# lessbadschematic.net
KiCad netlist of a schematic drawn in Altium Designer
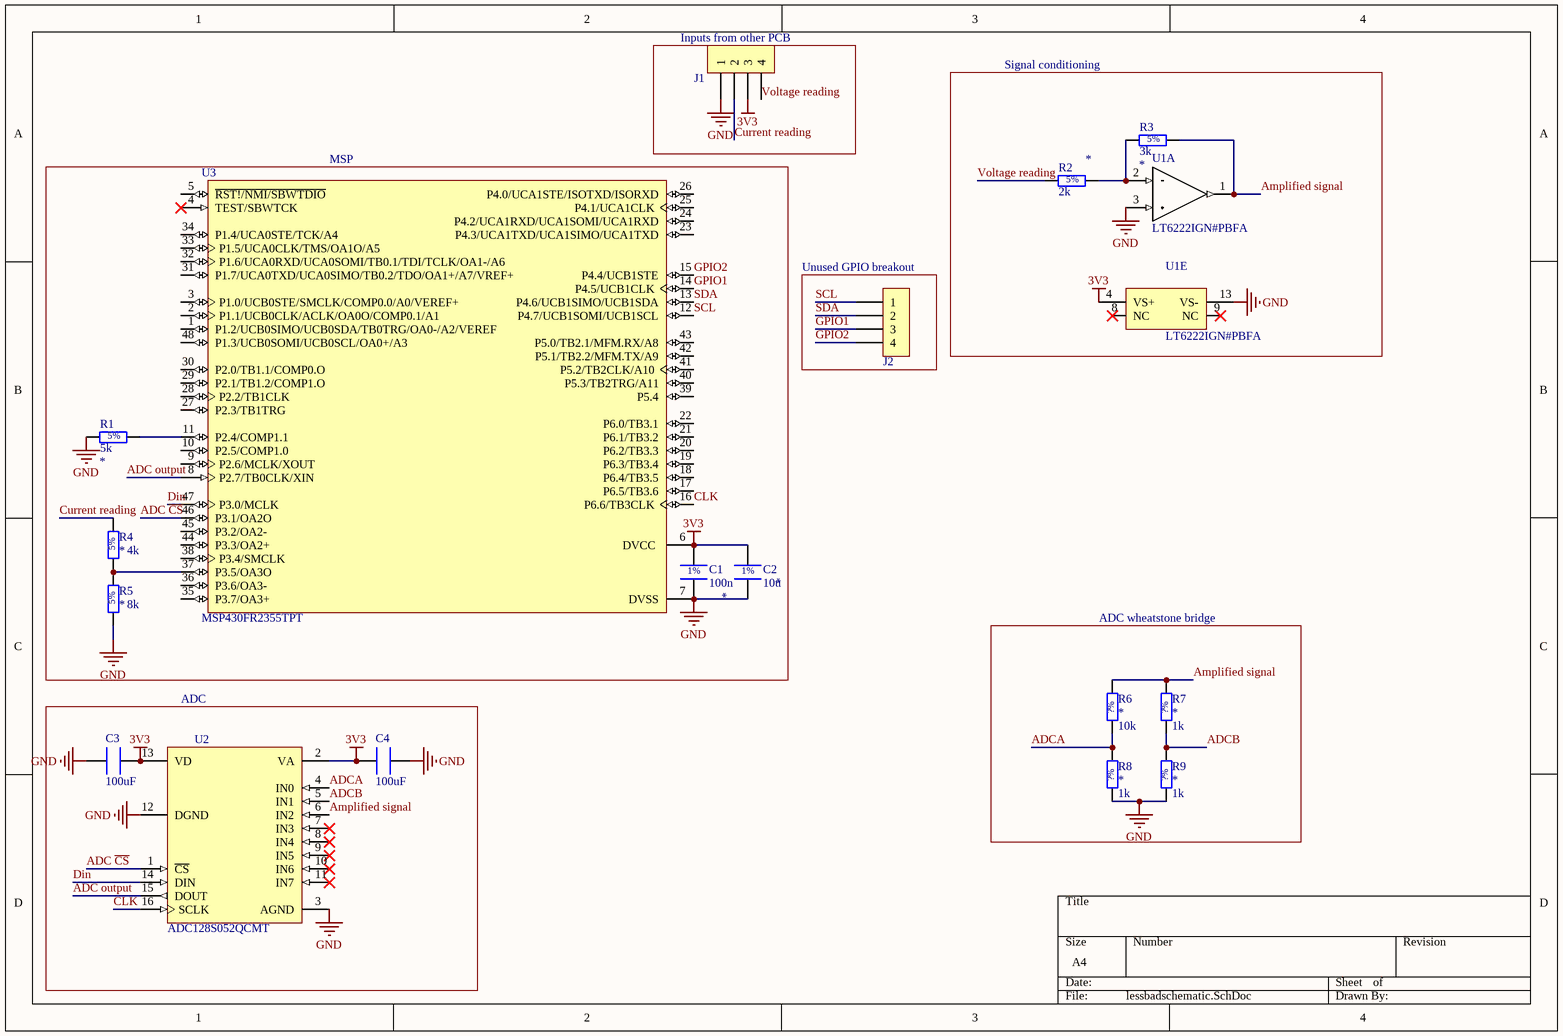
[diagram p0: lessbadschematic.SchDoc]

(export (version "E")
  (design (tool "Eeschema 10.0.6"))
  (components
    (comp (ref "C1")
      (value "100n")
      (footprint "APSS Flight Parts:CAPACITOR_0402_1005M_55N")
      (description "Passive - Capacitor Series, 0402, C0G, 50V, ±1%, -55°C ~ 125°C, 0402 (1005 Metric)")
      (fields (field (name "TOLERANCE") "±1%") (field (name "MF PART NO.") "*"))
      (libsource (lib "APSS Flight Parts") (part "GCM1555CxxxxxF Series"))
    )
    (comp (ref "C2")
      (value "10u")
      (footprint "APSS Flight Parts:CAPACITOR_0402_1005M_55N")
      (description "Passive - Capacitor Series, 0402, C0G, 50V, ±1%, -55°C ~ 125°C, 0402 (1005 Metric)")
      (fields (field (name "TOLERANCE") "±1%") (field (name "MF PART NO.") "*"))
      (libsource (lib "APSS Flight Parts") (part "GCM1555CxxxxxF Series"))
    )
    (comp (ref "C3")
      (value "100uF")
      (footprint "APSS Flight Parts:CAPACITOR_0805_2012M-70N")
      (fields (field (name "TOLERANCE") "±20%") (field (name "MF PART NO.") "GRM21BR60J107ME15L"))
      (libsource (lib "APSS Flight Parts") (part "GRM21BR60J107ME15L"))
    )
    (comp (ref "C4")
      (value "100uF")
      (footprint "APSS Flight Parts:CAPACITOR_0805_2012M-70N")
      (fields (field (name "TOLERANCE") "±20%") (field (name "MF PART NO.") "GRM21BR60J107ME15L"))
      (libsource (lib "APSS Flight Parts") (part "GRM21BR60J107ME15L"))
    )
    (comp (ref "J1")
      (value "0530470410")
      (footprint "APSS Flight Parts:MOLEX_0530470410")
      (description "Header - Picoblade 04-pin, TH, STR")
      (libsource (lib "") (part "0530470410_1"))
    )
    (comp (ref "J2")
      (value "0530470410")
      (footprint "APSS Flight Parts:MOLEX_0530470410")
      (description "Header - Picoblade 04-pin, TH, STR")
      (libsource (lib "APSS Flight Parts") (part "0530470410"))
    )
    (comp (ref "R1")
      (value "5k")
      (footprint "APSS Flight Parts:RESISTOR_0402_1005M_37N")
      (fields (field (name "TOLERANCE") "5%") (field (name "POWER") "1/16W") (field (name "MF PART NO.") "*"))
      (libsource (lib "APSS Flight Parts") (part "RMCF0402JT Series"))
    )
    (comp (ref "R2")
      (value "2k")
      (footprint "APSS Flight Parts:RESISTOR_0402_1005M_37N")
      (fields (field (name "TOLERANCE") "5%") (field (name "POWER") "1/16W") (field (name "MF PART NO.") "*"))
      (libsource (lib "APSS Flight Parts") (part "RMCF0402JT Series"))
    )
    (comp (ref "R3")
      (value "3k")
      (footprint "APSS Flight Parts:RESISTOR_0402_1005M_37N")
      (fields (field (name "TOLERANCE") "5%") (field (name "POWER") "1/16W") (field (name "MF PART NO.") "*"))
      (libsource (lib "APSS Flight Parts") (part "RMCF0402JT Series"))
    )
    (comp (ref "R4")
      (value "*")
      (footprint "APSS Flight Parts:Resistor_0805_2012M-50N")
      (fields
        (field (name "TOLERANCE") "5%")
        (field (name "POWER") "1/8W")
        (field (name "MF PART NO.") "4k")
        (field (name "ALTIUM_VALUE") "*")
      )
      (libsource (lib "APSS Flight Parts") (part "RMCF0805JT Series"))
    )
    (comp (ref "R5")
      (value "*")
      (footprint "APSS Flight Parts:Resistor_0805_2012M-50N")
      (fields
        (field (name "TOLERANCE") "5%")
        (field (name "POWER") "1/8W")
        (field (name "MF PART NO.") "8k")
        (field (name "ALTIUM_VALUE") "*")
      )
      (libsource (lib "APSS Flight Parts") (part "RMCF0805JT Series"))
    )
    (comp (ref "R6")
      (value "*")
      (footprint "RESISTOR_0805_2012M-50N")
      (description "Passive - Resistor, Generic")
      (fields
        (field (name "TOLERANCE") "?%")
        (field (name "MF PART NO.") "10k")
        (field (name "ALTIUM_VALUE") "*")
      )
      (libsource (lib "APSS Generic Components") (part "Generic Resistor"))
    )
    (comp (ref "R7")
      (value "*")
      (footprint "RESISTOR_0805_2012M-50N")
      (description "Passive - Resistor, Generic")
      (fields
        (field (name "TOLERANCE") "?%")
        (field (name "MF PART NO.") "1k")
        (field (name "ALTIUM_VALUE") "*")
      )
      (libsource (lib "APSS Generic Components") (part "Generic Resistor"))
    )
    (comp (ref "R8")
      (value "*")
      (footprint "RESISTOR_0805_2012M-50N")
      (description "Passive - Resistor, Generic")
      (fields
        (field (name "TOLERANCE") "?%")
        (field (name "MF PART NO.") "1k")
        (field (name "ALTIUM_VALUE") "*")
      )
      (libsource (lib "APSS Generic Components") (part "Generic Resistor"))
    )
    (comp (ref "R9")
      (value "*")
      (footprint "RESISTOR_0805_2012M-50N")
      (description "Passive - Resistor, Generic")
      (fields
        (field (name "TOLERANCE") "?%")
        (field (name "MF PART NO.") "1k")
        (field (name "ALTIUM_VALUE") "*")
      )
      (libsource (lib "APSS Generic Components") (part "Generic Resistor"))
    )
    (comp (ref "U1")
      (value "LT6222IGN#PBFA")
      (footprint "APSS Flight Parts:SSOP-16N-3.9mmBody-1.75mm")
      (description "IC - Opamp, High Speed, 4-Channel, 60MHz GBWP, RRIO, 2.2V to 12.6V, -40 to 85, SSOP-16")
      (fields (field (name "MF PART NO.") "LT6222IGN#PBF"))
      (libsource (lib "APSS Flight Parts") (part "LT6222IGN#PBF"))
    )
    (comp (ref "U2")
      (value "ADC128S052QCMT")
      (footprint "APSS Flight Parts:TSSOP-16N_4.4mmBody-1.2mm")
      (description "IC - ADC, 8-Channel, 12-bit, SPI, Split digital/analog Vcc")
      (fields (field (name "MF PART NO.") "ADC128S052QCMT/NOPB-ND"))
      (libsource (lib "APSS Flight Parts") (part "ADC128S052QCMT"))
    )
    (comp (ref "U3")
      (value "MSP430FR2355TPT")
      (footprint "APSS Flight Parts:LQFP_PT_48_N")
      (libsource (lib "APSS Flight Parts") (part "MSP430FR2355TPT"))
    )
  )
  (nets
    (net (code "1") (name "/ADC output") (class "Default")
      (node (ref "U2") (pin "15") (pinfunction "DOUT_15") (pintype "output"))
      (node (ref "U3") (pin "8") (pinfunction "P2.7/TB0CLK/XIN_8") (pintype "input"))
    )
    (net (code "2") (name "/ADC ~{CS}") (class "Default")
      (node (ref "U2") (pin "1") (pinfunction "~{CS}_1") (pintype "input"))
      (node (ref "U3") (pin "46") (pinfunction "P3.1/OA2O_46") (pintype "bidirectional"))
    )
    (net (code "3") (name "/ADCA") (class "Default")
      (node (ref "R6") (pin "1") (pinfunction "1_1") (pintype "passive"))
      (node (ref "R8") (pin "2") (pinfunction "2_2") (pintype "passive"))
      (node (ref "U2") (pin "4") (pinfunction "IN0_4") (pintype "input"))
    )
    (net (code "4") (name "/ADCB") (class "Default")
      (node (ref "R7") (pin "1") (pinfunction "1_1") (pintype "passive"))
      (node (ref "R9") (pin "2") (pinfunction "2_2") (pintype "passive"))
      (node (ref "U2") (pin "5") (pinfunction "IN1_5") (pintype "input"))
    )
    (net (code "5") (name "/Amplified signal") (class "Default")
      (node (ref "R3") (pin "2") (pinfunction "2_2") (pintype "passive"))
      (node (ref "R6") (pin "2") (pinfunction "2_2") (pintype "passive"))
      (node (ref "R7") (pin "2") (pinfunction "2_2") (pintype "passive"))
      (node (ref "U1") (pin "1") (pinfunction "OUT1_1") (pintype "output"))
      (node (ref "U2") (pin "6") (pinfunction "IN2_6") (pintype "input"))
    )
    (net (code "6") (name "/CLK") (class "Default")
      (node (ref "U2") (pin "16") (pinfunction "SCLK_16") (pintype "input"))
      (node (ref "U3") (pin "16") (pinfunction "P6.6/TB3CLK_16") (pintype "bidirectional"))
    )
    (net (code "7") (name "/Current reading") (class "Default")
      (node (ref "J1") (pin "2") (pinfunction "2_2") (pintype "passive"))
      (node (ref "R4") (pin "2") (pinfunction "2_2") (pintype "passive"))
    )
    (net (code "8") (name "/Din") (class "Default")
      (node (ref "U2") (pin "14") (pinfunction "DIN_14") (pintype "input"))
      (node (ref "U3") (pin "47") (pinfunction "P3.0/MCLK_47") (pintype "bidirectional"))
    )
    (net (code "9") (name "/GPIO1") (class "Default")
      (node (ref "J2") (pin "3") (pinfunction "3_3") (pintype "passive"))
      (node (ref "U3") (pin "14") (pinfunction "P4.5/UCB1CLK_14") (pintype "bidirectional"))
    )
    (net (code "10") (name "/GPIO2") (class "Default")
      (node (ref "J2") (pin "4") (pinfunction "4_4") (pintype "passive"))
      (node (ref "U3") (pin "15") (pinfunction "P4.4/UCB1STE_15") (pintype "bidirectional"))
    )
    (net (code "11") (name "/SCL") (class "Default")
      (node (ref "J2") (pin "1") (pinfunction "1_1") (pintype "passive"))
      (node (ref "U3") (pin "12") (pinfunction "P4.7/UCB1SOMI/UCB1SCL_12") (pintype "bidirectional"))
    )
    (net (code "12") (name "/SDA") (class "Default")
      (node (ref "J2") (pin "2") (pinfunction "2_2") (pintype "passive"))
      (node (ref "U3") (pin "13") (pinfunction "P4.6/UCB1SIMO/UCB1SDA_13") (pintype "bidirectional"))
    )
    (net (code "13") (name "/Voltage reading") (class "Default")
      (node (ref "J1") (pin "4") (pinfunction "4_4") (pintype "passive"))
      (node (ref "R2") (pin "1") (pinfunction "1_1") (pintype "passive"))
    )
    (net (code "14") (name "3V3") (class "Default")
      (node (ref "C1") (pin "2") (pinfunction "2_2") (pintype "passive"))
      (node (ref "C2") (pin "2") (pinfunction "2_2") (pintype "passive"))
      (node (ref "C3") (pin "2") (pinfunction "2_2") (pintype "passive"))
      (node (ref "C4") (pin "1") (pinfunction "1_1") (pintype "passive"))
      (node (ref "J1") (pin "3") (pinfunction "3_3") (pintype "passive"))
      (node (ref "U1") (pin "4") (pinfunction "VS+_4") (pintype "passive"))
      (node (ref "U2") (pin "13") (pinfunction "VD_13") (pintype "power_in"))
      (node (ref "U2") (pin "2") (pinfunction "VA_2") (pintype "power_in"))
      (node (ref "U3") (pin "6") (pinfunction "DVCC_6") (pintype "power_in"))
    )
    (net (code "15") (name "GND") (class "Default")
      (node (ref "C1") (pin "1") (pinfunction "1_1") (pintype "passive"))
      (node (ref "C2") (pin "1") (pinfunction "1_1") (pintype "passive"))
      (node (ref "C3") (pin "1") (pinfunction "1_1") (pintype "passive"))
      (node (ref "C4") (pin "2") (pinfunction "2_2") (pintype "passive"))
      (node (ref "J1") (pin "1") (pinfunction "1_1") (pintype "passive"))
      (node (ref "R1") (pin "1") (pinfunction "1_1") (pintype "passive"))
      (node (ref "R5") (pin "1") (pinfunction "1_1") (pintype "passive"))
      (node (ref "R8") (pin "1") (pinfunction "1_1") (pintype "passive"))
      (node (ref "R9") (pin "1") (pinfunction "1_1") (pintype "passive"))
      (node (ref "U1") (pin "13") (pinfunction "VS-_13") (pintype "passive"))
      (node (ref "U1") (pin "3") (pinfunction "IN1+_3") (pintype "input"))
      (node (ref "U2") (pin "12") (pinfunction "DGND_12") (pintype "passive"))
      (node (ref "U2") (pin "3") (pinfunction "AGND_3") (pintype "passive"))
      (node (ref "U3") (pin "7") (pinfunction "DVSS_7") (pintype "power_in"))
    )
    (net (code "16") (name "Net-(U1A-IN1-)") (class "Default")
      (node (ref "R2") (pin "2") (pinfunction "2_2") (pintype "passive"))
      (node (ref "R3") (pin "1") (pinfunction "1_1") (pintype "passive"))
      (node (ref "U1") (pin "2") (pinfunction "IN1-_2") (pintype "input"))
    )
    (net (code "17") (name "Net-(U3-P2.4{slash}COMP1.1)") (class "Default")
      (node (ref "R1") (pin "2") (pinfunction "2_2") (pintype "passive"))
      (node (ref "U3") (pin "11") (pinfunction "P2.4/COMP1.1_11") (pintype "bidirectional"))
    )
    (net (code "18") (name "Net-(U3-P3.5{slash}OA3O)") (class "Default")
      (node (ref "R4") (pin "1") (pinfunction "1_1") (pintype "passive"))
      (node (ref "R5") (pin "2") (pinfunction "2_2") (pintype "passive"))
      (node (ref "U3") (pin "37") (pinfunction "P3.5/OA3O_37") (pintype "bidirectional"))
    )
    (net (code "19") (name "unconnected-(U1E-NC-Pad8)") (class "Default")
      (node (ref "U1") (pin "8") (pinfunction "NC_8") (pintype "passive+no_connect"))
    )
    (net (code "20") (name "unconnected-(U1E-NC-Pad9)") (class "Default")
      (node (ref "U1") (pin "9") (pinfunction "NC_9") (pintype "passive+no_connect"))
    )
    (net (code "21") (name "unconnected-(U2-IN3-Pad7)") (class "Default")
      (node (ref "U2") (pin "7") (pinfunction "IN3_7") (pintype "input+no_connect"))
    )
    (net (code "22") (name "unconnected-(U2-IN4-Pad8)") (class "Default")
      (node (ref "U2") (pin "8") (pinfunction "IN4_8") (pintype "input+no_connect"))
    )
    (net (code "23") (name "unconnected-(U2-IN5-Pad9)") (class "Default")
      (node (ref "U2") (pin "9") (pinfunction "IN5_9") (pintype "input+no_connect"))
    )
    (net (code "24") (name "unconnected-(U2-IN6-Pad10)") (class "Default")
      (node (ref "U2") (pin "10") (pinfunction "IN6_10") (pintype "input+no_connect"))
    )
    (net (code "25") (name "unconnected-(U2-IN7-Pad11)") (class "Default")
      (node (ref "U2") (pin "11") (pinfunction "IN7_11") (pintype "input+no_connect"))
    )
    (net (code "26") (name "unconnected-(U3-P1.0{slash}UCB0STE{slash}SMCLK{slash}COMP0.0{slash}A0{slash}VEREF+-Pad3)") (class "Default")
      (node (ref "U3") (pin "3") (pinfunction "P1.0/UCB0STE/SMCLK/COMP0.0/A0/VEREF+_3") (pintype "bidirectional"))
    )
    (net (code "27") (name "unconnected-(U3-P1.1{slash}UCB0CLK{slash}ACLK{slash}OA0O{slash}COMP0.1{slash}A1-Pad2)") (class "Default")
      (node (ref "U3") (pin "2") (pinfunction "P1.1/UCB0CLK/ACLK/OA0O/COMP0.1/A1_2") (pintype "bidirectional"))
    )
    (net (code "28") (name "unconnected-(U3-P1.2{slash}UCB0SIMO{slash}UCB0SDA{slash}TB0TRG{slash}OA0-{slash}A2{slash}VEREF-Pad1)") (class "Default")
      (node (ref "U3") (pin "1") (pinfunction "P1.2/UCB0SIMO/UCB0SDA/TB0TRG/OA0-/A2/VEREF_1") (pintype "bidirectional"))
    )
    (net (code "29") (name "unconnected-(U3-P1.3{slash}UCB0SOMI{slash}UCB0SCL{slash}OA0+{slash}A3-Pad48)") (class "Default")
      (node (ref "U3") (pin "48") (pinfunction "P1.3/UCB0SOMI/UCB0SCL/OA0+/A3_48") (pintype "bidirectional"))
    )
    (net (code "30") (name "unconnected-(U3-P1.4{slash}UCA0STE{slash}TCK{slash}A4-Pad34)") (class "Default")
      (node (ref "U3") (pin "34") (pinfunction "P1.4/UCA0STE/TCK/A4_34") (pintype "bidirectional"))
    )
    (net (code "31") (name "unconnected-(U3-P1.5{slash}UCA0CLK{slash}TMS{slash}OA1O{slash}A5-Pad33)") (class "Default")
      (node (ref "U3") (pin "33") (pinfunction "P1.5/UCA0CLK/TMS/OA1O/A5_33") (pintype "bidirectional"))
    )
    (net (code "32") (name "unconnected-(U3-P1.6{slash}UCA0RXD{slash}UCA0SOMI{slash}TB0.1{slash}TDI{slash}TCLK{slash}OA1-{slash}A6-Pad32)") (class "Default")
      (node (ref "U3") (pin "32") (pinfunction "P1.6/UCA0RXD/UCA0SOMI/TB0.1/TDI/TCLK/OA1-/A6_32") (pintype "bidirectional"))
    )
    (net (code "33") (name "unconnected-(U3-P1.7{slash}UCA0TXD{slash}UCA0SIMO{slash}TB0.2{slash}TDO{slash}OA1+{slash}A7{slash}VREF+-Pad31)") (class "Default")
      (node (ref "U3") (pin "31") (pinfunction "P1.7/UCA0TXD/UCA0SIMO/TB0.2/TDO/OA1+/A7/VREF+_31") (pintype "bidirectional"))
    )
    (net (code "34") (name "unconnected-(U3-P2.0{slash}TB1.1{slash}COMP0.O-Pad30)") (class "Default")
      (node (ref "U3") (pin "30") (pinfunction "P2.0/TB1.1/COMP0.O_30") (pintype "bidirectional"))
    )
    (net (code "35") (name "unconnected-(U3-P2.1{slash}TB1.2{slash}COMP1.O-Pad29)") (class "Default")
      (node (ref "U3") (pin "29") (pinfunction "P2.1/TB1.2/COMP1.O_29") (pintype "bidirectional"))
    )
    (net (code "36") (name "unconnected-(U3-P2.2{slash}TB1CLK-Pad28)") (class "Default")
      (node (ref "U3") (pin "28") (pinfunction "P2.2/TB1CLK_28") (pintype "bidirectional"))
    )
    (net (code "37") (name "unconnected-(U3-P2.3{slash}TB1TRG-Pad27)") (class "Default")
      (node (ref "U3") (pin "27") (pinfunction "P2.3/TB1TRG_27") (pintype "bidirectional"))
    )
    (net (code "38") (name "unconnected-(U3-P2.5{slash}COMP1.0-Pad10)") (class "Default")
      (node (ref "U3") (pin "10") (pinfunction "P2.5/COMP1.0_10") (pintype "bidirectional"))
    )
    (net (code "39") (name "unconnected-(U3-P2.6{slash}MCLK{slash}XOUT-Pad9)") (class "Default")
      (node (ref "U3") (pin "9") (pinfunction "P2.6/MCLK/XOUT_9") (pintype "bidirectional"))
    )
    (net (code "40") (name "unconnected-(U3-P3.2{slash}OA2--Pad45)") (class "Default")
      (node (ref "U3") (pin "45") (pinfunction "P3.2/OA2-_45") (pintype "bidirectional"))
    )
    (net (code "41") (name "unconnected-(U3-P3.3{slash}OA2+-Pad44)") (class "Default")
      (node (ref "U3") (pin "44") (pinfunction "P3.3/OA2+_44") (pintype "bidirectional"))
    )
    (net (code "42") (name "unconnected-(U3-P3.4{slash}SMCLK-Pad38)") (class "Default")
      (node (ref "U3") (pin "38") (pinfunction "P3.4/SMCLK_38") (pintype "bidirectional"))
    )
    (net (code "43") (name "unconnected-(U3-P3.6{slash}OA3--Pad36)") (class "Default")
      (node (ref "U3") (pin "36") (pinfunction "P3.6/OA3-_36") (pintype "bidirectional"))
    )
    (net (code "44") (name "unconnected-(U3-P3.7{slash}OA3+-Pad35)") (class "Default")
      (node (ref "U3") (pin "35") (pinfunction "P3.7/OA3+_35") (pintype "bidirectional"))
    )
    (net (code "45") (name "unconnected-(U3-P4.0{slash}UCA1STE{slash}ISOTXD{slash}ISORXD-Pad26)") (class "Default")
      (node (ref "U3") (pin "26") (pinfunction "P4.0/UCA1STE/ISOTXD/ISORXD_26") (pintype "bidirectional"))
    )
    (net (code "46") (name "unconnected-(U3-P4.1{slash}UCA1CLK-Pad25)") (class "Default")
      (node (ref "U3") (pin "25") (pinfunction "P4.1/UCA1CLK_25") (pintype "bidirectional"))
    )
    (net (code "47") (name "unconnected-(U3-P4.2{slash}UCA1RXD{slash}UCA1SOMI{slash}UCA1RXD-Pad24)") (class "Default")
      (node (ref "U3") (pin "24") (pinfunction "P4.2/UCA1RXD/UCA1SOMI/UCA1RXD_24") (pintype "bidirectional"))
    )
    (net (code "48") (name "unconnected-(U3-P4.3{slash}UCA1TXD{slash}UCA1SIMO{slash}UCA1TXD-Pad23)") (class "Default")
      (node (ref "U3") (pin "23") (pinfunction "P4.3/UCA1TXD/UCA1SIMO/UCA1TXD_23") (pintype "bidirectional"))
    )
    (net (code "49") (name "unconnected-(U3-P5.0{slash}TB2.1{slash}MFM.RX{slash}A8-Pad43)") (class "Default")
      (node (ref "U3") (pin "43") (pinfunction "P5.0/TB2.1/MFM.RX/A8_43") (pintype "bidirectional"))
    )
    (net (code "50") (name "unconnected-(U3-P5.1{slash}TB2.2{slash}MFM.TX{slash}A9-Pad42)") (class "Default")
      (node (ref "U3") (pin "42") (pinfunction "P5.1/TB2.2/MFM.TX/A9_42") (pintype "bidirectional"))
    )
    (net (code "51") (name "unconnected-(U3-P5.2{slash}TB2CLK{slash}A10-Pad41)") (class "Default")
      (node (ref "U3") (pin "41") (pinfunction "P5.2/TB2CLK/A10_41") (pintype "bidirectional"))
    )
    (net (code "52") (name "unconnected-(U3-P5.3{slash}TB2TRG{slash}A11-Pad40)") (class "Default")
      (node (ref "U3") (pin "40") (pinfunction "P5.3/TB2TRG/A11_40") (pintype "bidirectional"))
    )
    (net (code "53") (name "unconnected-(U3-P5.4-Pad39)") (class "Default")
      (node (ref "U3") (pin "39") (pinfunction "P5.4_39") (pintype "bidirectional"))
    )
    (net (code "54") (name "unconnected-(U3-P6.0{slash}TB3.1-Pad22)") (class "Default")
      (node (ref "U3") (pin "22") (pinfunction "P6.0/TB3.1_22") (pintype "bidirectional"))
    )
    (net (code "55") (name "unconnected-(U3-P6.1{slash}TB3.2-Pad21)") (class "Default")
      (node (ref "U3") (pin "21") (pinfunction "P6.1/TB3.2_21") (pintype "bidirectional"))
    )
    (net (code "56") (name "unconnected-(U3-P6.2{slash}TB3.3-Pad20)") (class "Default")
      (node (ref "U3") (pin "20") (pinfunction "P6.2/TB3.3_20") (pintype "bidirectional"))
    )
    (net (code "57") (name "unconnected-(U3-P6.3{slash}TB3.4-Pad19)") (class "Default")
      (node (ref "U3") (pin "19") (pinfunction "P6.3/TB3.4_19") (pintype "bidirectional"))
    )
    (net (code "58") (name "unconnected-(U3-P6.4{slash}TB3.5-Pad18)") (class "Default")
      (node (ref "U3") (pin "18") (pinfunction "P6.4/TB3.5_18") (pintype "bidirectional"))
    )
    (net (code "59") (name "unconnected-(U3-P6.5{slash}TB3.6-Pad17)") (class "Default")
      (node (ref "U3") (pin "17") (pinfunction "P6.5/TB3.6_17") (pintype "bidirectional"))
    )
    (net (code "60") (name "unconnected-(U3-TEST{slash}SBWTCK-Pad4)") (class "Default")
      (node (ref "U3") (pin "4") (pinfunction "TEST/SBWTCK_4") (pintype "input+no_connect"))
    )
    (net (code "61") (name "unconnected-(U3-~{RST!{slash}NMI{slash}SBWTDIO}-Pad5)") (class "Default")
      (node (ref "U3") (pin "5") (pinfunction "~{RST!/NMI/SBWTDIO}_5") (pintype "bidirectional"))
    )
  )
)
